# rpiInterface.net
KiCad netlist of a schematic drawn in EAGLE
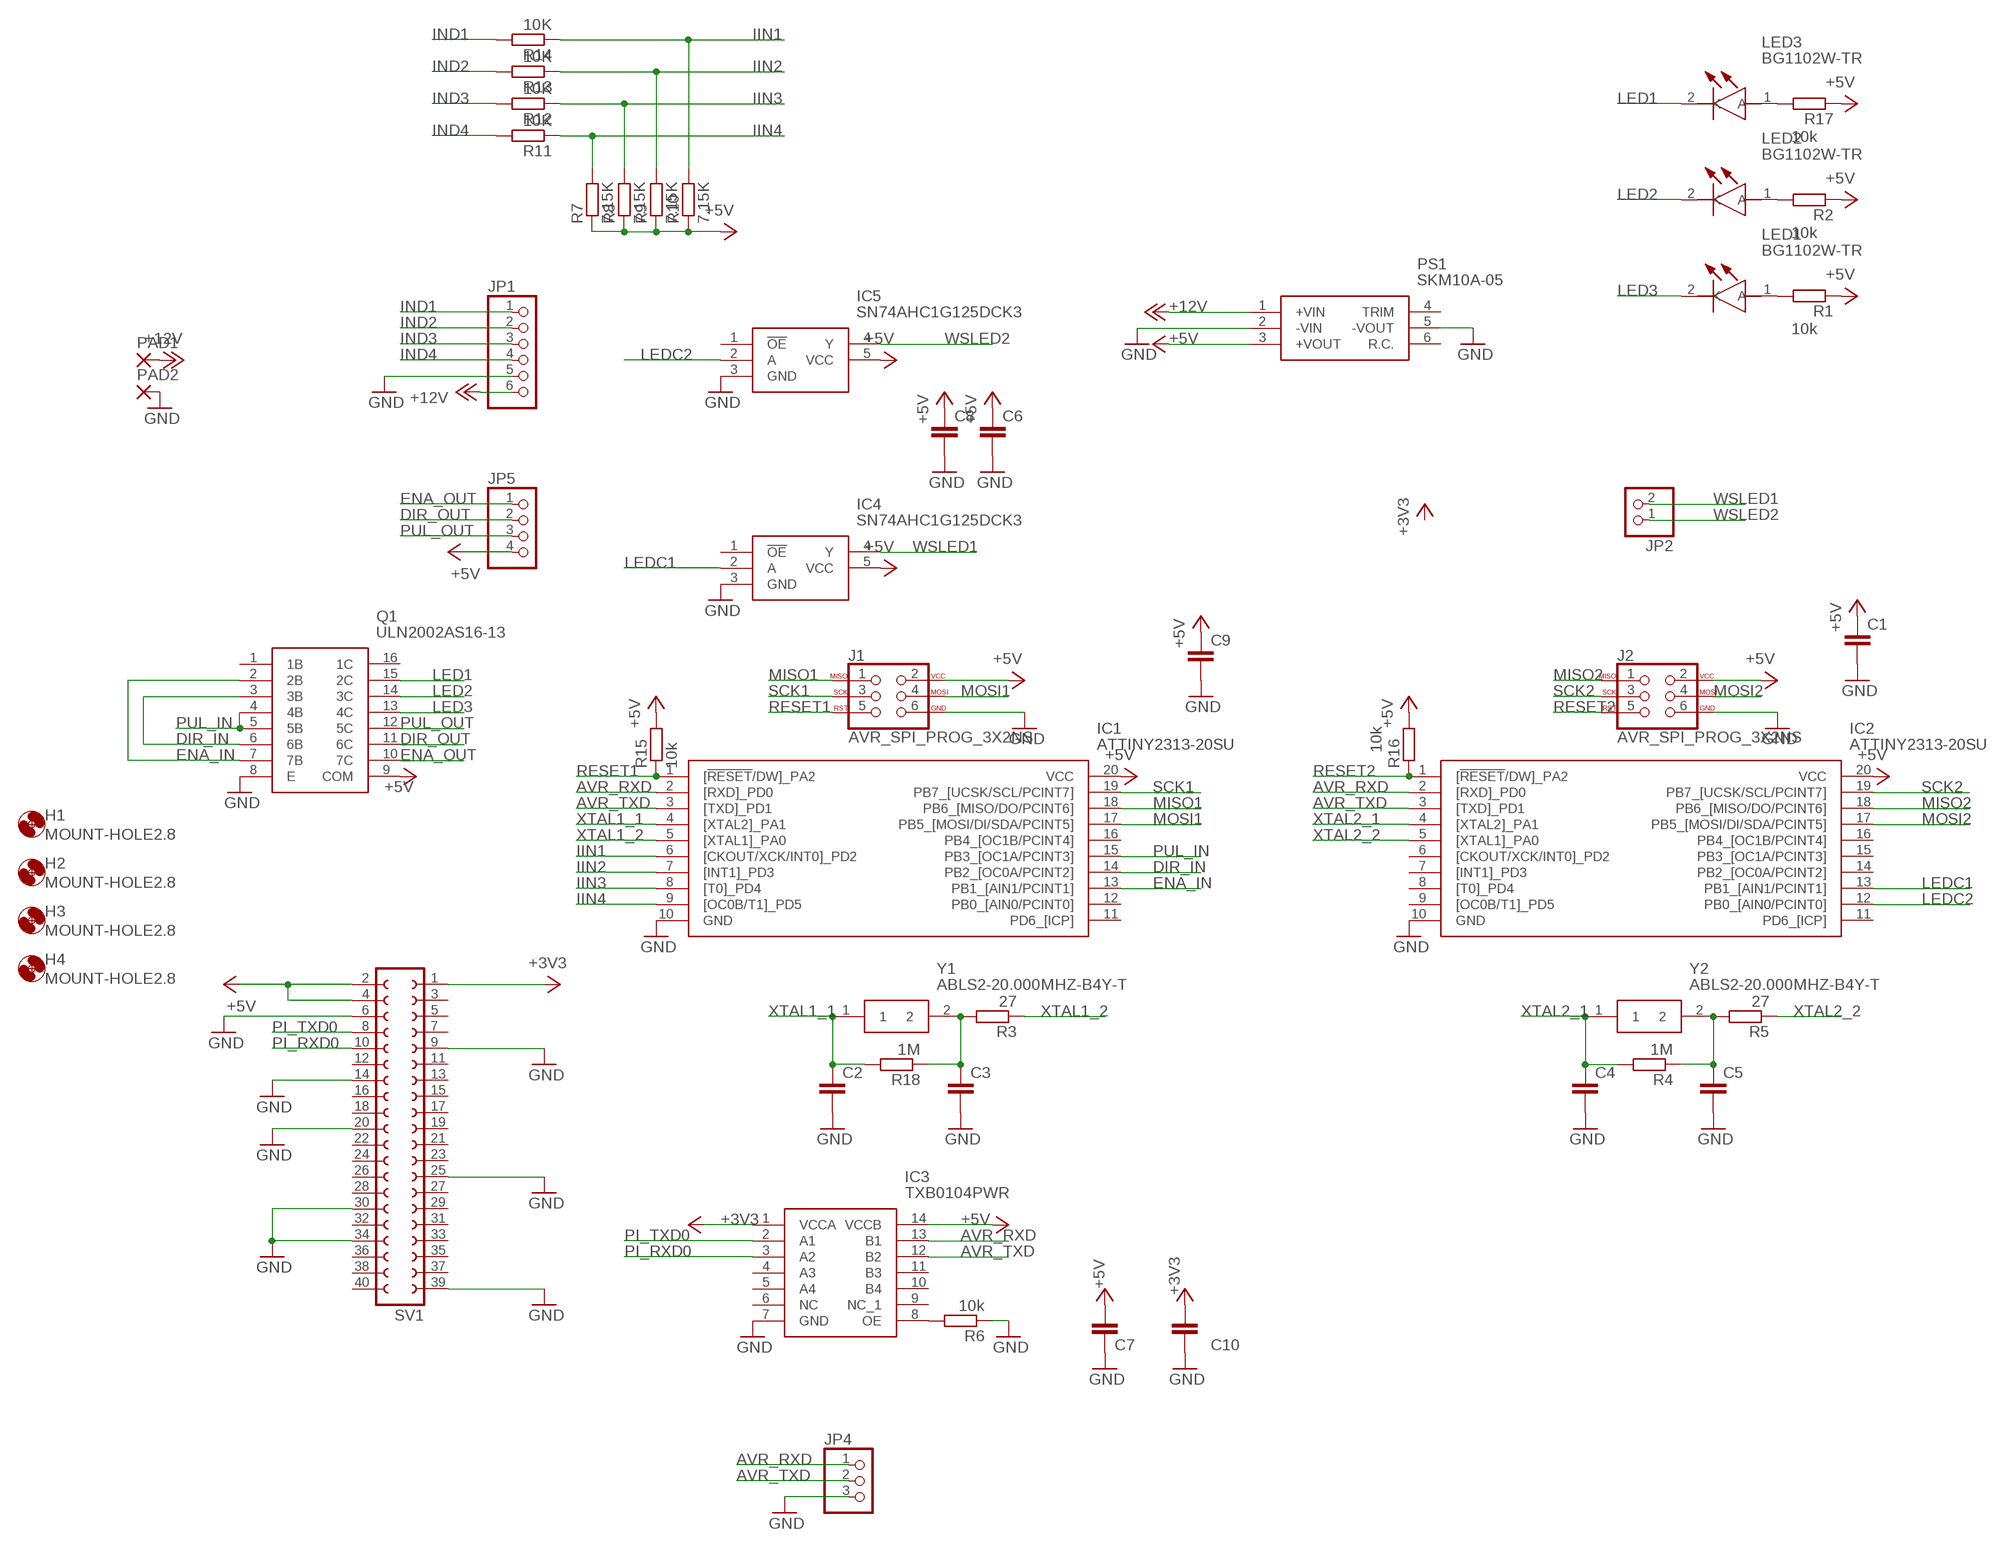
[diagram p0: schematic, sheet 1]

(export (version "E")
  (design (tool "Eeschema 10.0.6"))
  (components
    (comp (ref "C1")
      (value "C-EUC1206")
      (footprint "eagle-import:C1206")
      (libsource (lib "eagle-import") (part "C-EUC1206"))
    )
    (comp (ref "C2")
      (value "C-EUC1206")
      (footprint "eagle-import:C1206")
      (libsource (lib "eagle-import") (part "C-EUC1206"))
    )
    (comp (ref "C3")
      (value "C-EUC1206")
      (footprint "eagle-import:C1206")
      (libsource (lib "eagle-import") (part "C-EUC1206"))
    )
    (comp (ref "C4")
      (value "C-EUC1206")
      (footprint "eagle-import:C1206")
      (libsource (lib "eagle-import") (part "C-EUC1206"))
    )
    (comp (ref "C5")
      (value "C-EUC1206")
      (footprint "eagle-import:C1206")
      (libsource (lib "eagle-import") (part "C-EUC1206"))
    )
    (comp (ref "C6")
      (value "C-EUC1206")
      (footprint "eagle-import:C1206")
      (libsource (lib "eagle-import") (part "C-EUC1206"))
    )
    (comp (ref "C7")
      (value "C-EUC1206")
      (footprint "eagle-import:C1206")
      (libsource (lib "eagle-import") (part "C-EUC1206"))
    )
    (comp (ref "C8")
      (value "C-EUC1206")
      (footprint "eagle-import:C1206")
      (libsource (lib "eagle-import") (part "C-EUC1206"))
    )
    (comp (ref "C9")
      (value "C-EUC1206")
      (footprint "eagle-import:C1206")
      (libsource (lib "eagle-import") (part "C-EUC1206"))
    )
    (comp (ref "C10")
      (value "C-EUC1206")
      (footprint "eagle-import:C1206")
      (libsource (lib "eagle-import") (part "C-EUC1206"))
    )
    (comp (ref "H1")
      (value "MOUNT-HOLE2.8")
      (footprint "eagle-import:2,8")
      (libsource (lib "eagle-import") (part "MOUNT-HOLE2.8"))
    )
    (comp (ref "H2")
      (value "MOUNT-HOLE2.8")
      (footprint "eagle-import:2,8")
      (libsource (lib "eagle-import") (part "MOUNT-HOLE2.8"))
    )
    (comp (ref "H3")
      (value "MOUNT-HOLE2.8")
      (footprint "eagle-import:2,8")
      (libsource (lib "eagle-import") (part "MOUNT-HOLE2.8"))
    )
    (comp (ref "H4")
      (value "MOUNT-HOLE2.8")
      (footprint "eagle-import:2,8")
      (libsource (lib "eagle-import") (part "MOUNT-HOLE2.8"))
    )
    (comp (ref "IC1")
      (value "ATTINY2313-20SU")
      (footprint "eagle-import:SOIC127P1032X265-20N")
      (fields (field (name "MOUSER_PART_NUMBER") "556-ATTINY2313-20SU"))
      (libsource (lib "eagle-import") (part "ATTINY2313-20SU"))
    )
    (comp (ref "IC2")
      (value "ATTINY2313-20SU")
      (footprint "eagle-import:SOIC127P1032X265-20N")
      (fields (field (name "MOUSER_PART_NUMBER") "556-ATTINY2313-20SU"))
      (libsource (lib "eagle-import") (part "ATTINY2313-20SU"))
    )
    (comp (ref "IC3")
      (value "TXB0104PWR")
      (footprint "eagle-import:SOP65P640X120-14N")
      (fields (field (name "MOUSER_PART_NUMBER") "595-TXB0104PWR"))
      (libsource (lib "eagle-import") (part "TXB0104PWR"))
    )
    (comp (ref "IC4")
      (value "SN74AHC1G125DCK3")
      (footprint "eagle-import:SOT65P210X110-5N")
      (fields (field (name "MOUSER_PART_NUMBER") "595-SN74AHC1G125DCK3"))
      (libsource (lib "eagle-import") (part "SN74AHC1G125DCK3"))
    )
    (comp (ref "IC5")
      (value "SN74AHC1G125DCK3")
      (footprint "eagle-import:SOT65P210X110-5N")
      (fields (field (name "MOUSER_PART_NUMBER") "595-SN74AHC1G125DCK3"))
      (libsource (lib "eagle-import") (part "SN74AHC1G125DCK3"))
    )
    (comp (ref "J1")
      (value "AVR_SPI_PROG_3X2NS")
      (footprint "eagle-import:2X3-NS")
      (libsource (lib "eagle-import") (part "AVR_SPI_PROG_3X2NS"))
    )
    (comp (ref "J2")
      (value "AVR_SPI_PROG_3X2NS")
      (footprint "eagle-import:2X3-NS")
      (libsource (lib "eagle-import") (part "AVR_SPI_PROG_3X2NS"))
    )
    (comp (ref "JP1")
      (value "PINHD-1X6")
      (footprint "eagle-import:1X06")
      (libsource (lib "eagle-import") (part "PINHD-1X6"))
    )
    (comp (ref "JP2")
      (value "PINHD-1X2")
      (footprint "eagle-import:1X02")
      (libsource (lib "eagle-import") (part "PINHD-1X2"))
    )
    (comp (ref "JP4")
      (value "PINHD-1X3")
      (footprint "eagle-import:1X03")
      (libsource (lib "eagle-import") (part "PINHD-1X3"))
    )
    (comp (ref "JP5")
      (value "PINHD-1X4")
      (footprint "eagle-import:1X04")
      (libsource (lib "eagle-import") (part "PINHD-1X4"))
    )
    (comp (ref "LED1")
      (value "BG1102W-TR")
      (footprint "eagle-import:BG1102WTR")
      (fields (field (name "MOUSER_PART_NUMBER") "327-BG1102WTR"))
      (libsource (lib "eagle-import") (part "BG1102W-TR"))
    )
    (comp (ref "LED2")
      (value "BG1102W-TR")
      (footprint "eagle-import:BG1102WTR")
      (fields (field (name "MOUSER_PART_NUMBER") "327-BG1102WTR"))
      (libsource (lib "eagle-import") (part "BG1102W-TR"))
    )
    (comp (ref "LED3")
      (value "BG1102W-TR")
      (footprint "eagle-import:BG1102WTR")
      (fields (field (name "MOUSER_PART_NUMBER") "327-BG1102WTR"))
      (libsource (lib "eagle-import") (part "BG1102W-TR"))
    )
    (comp (ref "PAD1")
      (value "3,17/1,3")
      (footprint "eagle-import:3,17_1,3")
      (libsource (lib "eagle-import") (part "3,17/1,3"))
    )
    (comp (ref "PAD2")
      (value "3,17/1,3")
      (footprint "eagle-import:3,17_1,3")
      (libsource (lib "eagle-import") (part "3,17/1,3"))
    )
    (comp (ref "PS1")
      (value "SKM10A-05")
      (footprint "eagle-import:SKM10A05")
      (fields (field (name "MOUSER_PART_NUMBER") "709-SKM10A-05"))
      (libsource (lib "eagle-import") (part "SKM10A-05"))
    )
    (comp (ref "Q1")
      (value "ULN2002AS16-13")
      (footprint "eagle-import:SOIC127P605X126-16N")
      (fields (field (name "MOUSER_PART_NUMBER") "621-ULN2002AS16-13"))
      (libsource (lib "eagle-import") (part "ULN2002AS16-13"))
    )
    (comp (ref "R1")
      (value "10k")
      (footprint "eagle-import:R1206")
      (libsource (lib "eagle-import") (part "R-EU_R1206"))
    )
    (comp (ref "R2")
      (value "10k")
      (footprint "eagle-import:R1206")
      (libsource (lib "eagle-import") (part "R-EU_R1206"))
    )
    (comp (ref "R3")
      (value "27")
      (footprint "eagle-import:R1206")
      (libsource (lib "eagle-import") (part "R-EU_R1206"))
    )
    (comp (ref "R4")
      (value "1M")
      (footprint "eagle-import:R1206")
      (libsource (lib "eagle-import") (part "R-EU_R1206"))
    )
    (comp (ref "R5")
      (value "27")
      (footprint "eagle-import:R1206")
      (libsource (lib "eagle-import") (part "R-EU_R1206"))
    )
    (comp (ref "R6")
      (value "10k")
      (footprint "eagle-import:R1206")
      (libsource (lib "eagle-import") (part "R-EU_R1206"))
    )
    (comp (ref "R7")
      (value "7.15K")
      (footprint "eagle-import:R1206")
      (libsource (lib "eagle-import") (part "R-EU_R1206"))
    )
    (comp (ref "R8")
      (value "7.15K")
      (footprint "eagle-import:R1206")
      (libsource (lib "eagle-import") (part "R-EU_R1206"))
    )
    (comp (ref "R9")
      (value "7.15K")
      (footprint "eagle-import:R1206")
      (libsource (lib "eagle-import") (part "R-EU_R1206"))
    )
    (comp (ref "R10")
      (value "7.15K")
      (footprint "eagle-import:R1206")
      (libsource (lib "eagle-import") (part "R-EU_R1206"))
    )
    (comp (ref "R11")
      (value "10K")
      (footprint "eagle-import:R1206")
      (libsource (lib "eagle-import") (part "R-EU_R1206"))
    )
    (comp (ref "R12")
      (value "10K")
      (footprint "eagle-import:R1206")
      (libsource (lib "eagle-import") (part "R-EU_R1206"))
    )
    (comp (ref "R13")
      (value "10K")
      (footprint "eagle-import:R1206")
      (libsource (lib "eagle-import") (part "R-EU_R1206"))
    )
    (comp (ref "R14")
      (value "10K")
      (footprint "eagle-import:R1206")
      (libsource (lib "eagle-import") (part "R-EU_R1206"))
    )
    (comp (ref "R15")
      (value "10k")
      (footprint "eagle-import:R1206")
      (libsource (lib "eagle-import") (part "R-EU_R1206"))
    )
    (comp (ref "R16")
      (value "10k")
      (footprint "eagle-import:R1206")
      (libsource (lib "eagle-import") (part "R-EU_R1206"))
    )
    (comp (ref "R17")
      (value "10k")
      (footprint "eagle-import:R1206")
      (libsource (lib "eagle-import") (part "R-EU_R1206"))
    )
    (comp (ref "R18")
      (value "1M")
      (footprint "eagle-import:R1206")
      (libsource (lib "eagle-import") (part "R-EU_R1206"))
    )
    (comp (ref "SV1")
      (value "FE20-2")
      (footprint "eagle-import:FE20-2")
      (libsource (lib "eagle-import") (part "FE20-2"))
    )
    (comp (ref "Y1")
      (value "ABLS2-20.000MHZ-B4Y-T")
      (footprint "eagle-import:HC_49US-(AT49)_1")
      (fields
        (field (name "MANUFACTURER_PART_NUMBER") "ABLS2-20.000MHz-B4Y-T")
        (field (name "MOUSER_PART_NUMBER") "815-ABLS2-20-B4YT")
      )
      (libsource (lib "eagle-import") (part "ABLS2-20.000MHZ-B4Y-T"))
    )
    (comp (ref "Y2")
      (value "ABLS2-20.000MHZ-B4Y-T")
      (footprint "eagle-import:HC_49US-(AT49)_1")
      (fields
        (field (name "MANUFACTURER_PART_NUMBER") "ABLS2-20.000MHz-B4Y-T")
        (field (name "MOUSER_PART_NUMBER") "815-ABLS2-20-B4YT")
      )
      (libsource (lib "eagle-import") (part "ABLS2-20.000MHZ-B4Y-T"))
    )
  )
  (nets
    (net (code "1") (name "+3V3") (class "Default")
      (node (ref "C10") (pin "1") (pinfunction "1_1") (pintype "passive"))
      (node (ref "IC3") (pin "1") (pinfunction "VCCA_1") (pintype "power_in"))
      (node (ref "SV1") (pin "1") (pinfunction "1_1") (pintype "passive"))
    )
    (net (code "2") (name "+5V") (class "Default")
      (node (ref "C1") (pin "1") (pinfunction "1_1") (pintype "passive"))
      (node (ref "C6") (pin "1") (pinfunction "1_1") (pintype "passive"))
      (node (ref "C7") (pin "1") (pinfunction "1_1") (pintype "passive"))
      (node (ref "C8") (pin "1") (pinfunction "1_1") (pintype "passive"))
      (node (ref "C9") (pin "1") (pinfunction "1_1") (pintype "passive"))
      (node (ref "IC1") (pin "20") (pinfunction "VCC_20") (pintype "power_in"))
      (node (ref "IC2") (pin "20") (pinfunction "VCC_20") (pintype "power_in"))
      (node (ref "IC3") (pin "14") (pinfunction "VCCB_14") (pintype "power_in"))
      (node (ref "IC4") (pin "5") (pinfunction "VCC_5") (pintype "bidirectional"))
      (node (ref "IC5") (pin "5") (pinfunction "VCC_5") (pintype "bidirectional"))
      (node (ref "J1") (pin "2") (pinfunction "2_2") (pintype "passive"))
      (node (ref "J2") (pin "2") (pinfunction "2_2") (pintype "passive"))
      (node (ref "JP5") (pin "4") (pinfunction "4_4") (pintype "passive"))
      (node (ref "PS1") (pin "3") (pinfunction "+VOUT_3") (pintype "bidirectional"))
      (node (ref "Q1") (pin "9") (pinfunction "COM_9") (pintype "bidirectional"))
      (node (ref "R1") (pin "1") (pinfunction "1_1") (pintype "passive"))
      (node (ref "R10") (pin "1") (pinfunction "1_1") (pintype "passive"))
      (node (ref "R15") (pin "2") (pinfunction "2_2") (pintype "passive"))
      (node (ref "R16") (pin "2") (pinfunction "2_2") (pintype "passive"))
      (node (ref "R17") (pin "1") (pinfunction "1_1") (pintype "passive"))
      (node (ref "R2") (pin "1") (pinfunction "1_1") (pintype "passive"))
      (node (ref "R7") (pin "1") (pinfunction "1_1") (pintype "passive"))
      (node (ref "R8") (pin "1") (pinfunction "1_1") (pintype "passive"))
      (node (ref "R9") (pin "1") (pinfunction "1_1") (pintype "passive"))
      (node (ref "SV1") (pin "2") (pinfunction "2_2") (pintype "passive"))
      (node (ref "SV1") (pin "4") (pinfunction "4_4") (pintype "passive"))
    )
    (net (code "3") (name "+12V") (class "Default")
      (node (ref "JP1") (pin "6") (pinfunction "6_6") (pintype "passive"))
      (node (ref "PAD1") (pin "1") (pinfunction "P_1") (pintype "passive"))
      (node (ref "PS1") (pin "1") (pinfunction "+VIN_1") (pintype "bidirectional"))
    )
    (net (code "4") (name "/AVR_RXD") (class "Default")
      (node (ref "IC1") (pin "2") (pinfunction "[RXD]_PD0_2") (pintype "bidirectional"))
      (node (ref "IC2") (pin "2") (pinfunction "[RXD]_PD0_2") (pintype "bidirectional"))
      (node (ref "IC3") (pin "13") (pinfunction "B1_13") (pintype "bidirectional"))
      (node (ref "JP4") (pin "1") (pinfunction "1_1") (pintype "passive"))
    )
    (net (code "5") (name "/AVR_TXD") (class "Default")
      (node (ref "IC1") (pin "3") (pinfunction "[TXD]_PD1_3") (pintype "bidirectional"))
      (node (ref "IC2") (pin "3") (pinfunction "[TXD]_PD1_3") (pintype "bidirectional"))
      (node (ref "IC3") (pin "12") (pinfunction "B2_12") (pintype "bidirectional"))
      (node (ref "JP4") (pin "2") (pinfunction "2_2") (pintype "passive"))
    )
    (net (code "6") (name "/DIR_IN") (class "Default")
      (node (ref "IC1") (pin "14") (pinfunction "PB2_[OC0A/PCINT2]_14") (pintype "input"))
      (node (ref "Q1") (pin "3") (pinfunction "3B_3") (pintype "bidirectional"))
      (node (ref "Q1") (pin "6") (pinfunction "6B_6") (pintype "bidirectional"))
    )
    (net (code "7") (name "/DIR_OUT") (class "Default")
      (node (ref "JP5") (pin "2") (pinfunction "2_2") (pintype "passive"))
      (node (ref "Q1") (pin "11") (pinfunction "6C_11") (pintype "bidirectional"))
    )
    (net (code "8") (name "/ENA_IN") (class "Default")
      (node (ref "IC1") (pin "13") (pinfunction "PB1_[AIN1/PCINT1]_13") (pintype "input"))
      (node (ref "Q1") (pin "2") (pinfunction "2B_2") (pintype "bidirectional"))
      (node (ref "Q1") (pin "7") (pinfunction "7B_7") (pintype "bidirectional"))
    )
    (net (code "9") (name "/ENA_OUT") (class "Default")
      (node (ref "JP5") (pin "1") (pinfunction "1_1") (pintype "passive"))
      (node (ref "Q1") (pin "10") (pinfunction "7C_10") (pintype "bidirectional"))
    )
    (net (code "10") (name "/IIN1") (class "Default")
      (node (ref "IC1") (pin "6") (pinfunction "[CKOUT/XCK/INT0]_PD2_6") (pintype "output"))
      (node (ref "R10") (pin "2") (pinfunction "2_2") (pintype "passive"))
      (node (ref "R14") (pin "1") (pinfunction "1_1") (pintype "passive"))
    )
    (net (code "11") (name "/IIN2") (class "Default")
      (node (ref "IC1") (pin "7") (pinfunction "[INT1]_PD3_7") (pintype "input"))
      (node (ref "R13") (pin "1") (pinfunction "1_1") (pintype "passive"))
      (node (ref "R9") (pin "2") (pinfunction "2_2") (pintype "passive"))
    )
    (net (code "12") (name "/IIN3") (class "Default")
      (node (ref "IC1") (pin "8") (pinfunction "[T0]_PD4_8") (pintype "bidirectional"))
      (node (ref "R12") (pin "1") (pinfunction "1_1") (pintype "passive"))
      (node (ref "R8") (pin "2") (pinfunction "2_2") (pintype "passive"))
    )
    (net (code "13") (name "/IIN4") (class "Default")
      (node (ref "IC1") (pin "9") (pinfunction "[OC0B/T1]_PD5_9") (pintype "bidirectional"))
      (node (ref "R11") (pin "1") (pinfunction "1_1") (pintype "passive"))
      (node (ref "R7") (pin "2") (pinfunction "2_2") (pintype "passive"))
    )
    (net (code "14") (name "/IND1") (class "Default")
      (node (ref "JP1") (pin "1") (pinfunction "1_1") (pintype "passive"))
      (node (ref "R14") (pin "2") (pinfunction "2_2") (pintype "passive"))
    )
    (net (code "15") (name "/IND2") (class "Default")
      (node (ref "JP1") (pin "2") (pinfunction "2_2") (pintype "passive"))
      (node (ref "R13") (pin "2") (pinfunction "2_2") (pintype "passive"))
    )
    (net (code "16") (name "/IND3") (class "Default")
      (node (ref "JP1") (pin "3") (pinfunction "3_3") (pintype "passive"))
      (node (ref "R12") (pin "2") (pinfunction "2_2") (pintype "passive"))
    )
    (net (code "17") (name "/IND4") (class "Default")
      (node (ref "JP1") (pin "4") (pinfunction "4_4") (pintype "passive"))
      (node (ref "R11") (pin "2") (pinfunction "2_2") (pintype "passive"))
    )
    (net (code "18") (name "/LED1") (class "Default")
      (node (ref "LED3") (pin "2") (pinfunction "K_2") (pintype "bidirectional"))
      (node (ref "Q1") (pin "15") (pinfunction "2C_15") (pintype "bidirectional"))
    )
    (net (code "19") (name "/LED2") (class "Default")
      (node (ref "LED2") (pin "2") (pinfunction "K_2") (pintype "bidirectional"))
      (node (ref "Q1") (pin "14") (pinfunction "3C_14") (pintype "bidirectional"))
    )
    (net (code "20") (name "/LED3") (class "Default")
      (node (ref "LED1") (pin "2") (pinfunction "K_2") (pintype "bidirectional"))
      (node (ref "Q1") (pin "13") (pinfunction "4C_13") (pintype "bidirectional"))
    )
    (net (code "21") (name "/LEDC1") (class "Default")
      (node (ref "IC2") (pin "13") (pinfunction "PB1_[AIN1/PCINT1]_13") (pintype "input"))
      (node (ref "IC4") (pin "2") (pinfunction "A_2") (pintype "bidirectional"))
    )
    (net (code "22") (name "/LEDC2") (class "Default")
      (node (ref "IC2") (pin "12") (pinfunction "PB0_[AIN0/PCINT0]_12") (pintype "input"))
      (node (ref "IC5") (pin "2") (pinfunction "A_2") (pintype "bidirectional"))
    )
    (net (code "23") (name "/MISO1") (class "Default")
      (node (ref "IC1") (pin "18") (pinfunction "PB6_[MISO/DO/PCINT6]_18") (pintype "input"))
      (node (ref "J1") (pin "1") (pinfunction "1_1") (pintype "passive"))
    )
    (net (code "24") (name "/MISO2") (class "Default")
      (node (ref "IC2") (pin "18") (pinfunction "PB6_[MISO/DO/PCINT6]_18") (pintype "input"))
      (node (ref "J2") (pin "1") (pinfunction "1_1") (pintype "passive"))
    )
    (net (code "25") (name "/MOSI1") (class "Default")
      (node (ref "IC1") (pin "17") (pinfunction "PB5_[MOSI/DI/SDA/PCINT5]_17") (pintype "input"))
      (node (ref "J1") (pin "4") (pinfunction "4_4") (pintype "passive"))
    )
    (net (code "26") (name "/MOSI2") (class "Default")
      (node (ref "IC2") (pin "17") (pinfunction "PB5_[MOSI/DI/SDA/PCINT5]_17") (pintype "input"))
      (node (ref "J2") (pin "4") (pinfunction "4_4") (pintype "passive"))
    )
    (net (code "27") (name "/PI_RXD0") (class "Default")
      (node (ref "IC3") (pin "3") (pinfunction "A2_3") (pintype "bidirectional"))
      (node (ref "SV1") (pin "10") (pinfunction "10_10") (pintype "passive"))
    )
    (net (code "28") (name "/PI_TXD0") (class "Default")
      (node (ref "IC3") (pin "2") (pinfunction "A1_2") (pintype "bidirectional"))
      (node (ref "SV1") (pin "8") (pinfunction "8_8") (pintype "passive"))
    )
    (net (code "29") (name "/PUL_IN") (class "Default")
      (node (ref "IC1") (pin "15") (pinfunction "PB3_[OC1A/PCINT3]_15") (pintype "input"))
      (node (ref "Q1") (pin "4") (pinfunction "4B_4") (pintype "bidirectional"))
      (node (ref "Q1") (pin "5") (pinfunction "5B_5") (pintype "bidirectional"))
    )
    (net (code "30") (name "/PUL_OUT") (class "Default")
      (node (ref "JP5") (pin "3") (pinfunction "3_3") (pintype "passive"))
      (node (ref "Q1") (pin "12") (pinfunction "5C_12") (pintype "bidirectional"))
    )
    (net (code "31") (name "/RESET1") (class "Default")
      (node (ref "IC1") (pin "1") (pinfunction "[~{RESET}/DW]_PA2_1") (pintype "bidirectional"))
      (node (ref "J1") (pin "5") (pinfunction "5_5") (pintype "passive"))
      (node (ref "R15") (pin "1") (pinfunction "1_1") (pintype "passive"))
    )
    (net (code "32") (name "/RESET2") (class "Default")
      (node (ref "IC2") (pin "1") (pinfunction "[~{RESET}/DW]_PA2_1") (pintype "bidirectional"))
      (node (ref "J2") (pin "5") (pinfunction "5_5") (pintype "passive"))
      (node (ref "R16") (pin "1") (pinfunction "1_1") (pintype "passive"))
    )
    (net (code "33") (name "/SCK1") (class "Default")
      (node (ref "IC1") (pin "19") (pinfunction "PB7_[UCSK/SCL/PCINT7]_19") (pintype "input"))
      (node (ref "J1") (pin "3") (pinfunction "3_3") (pintype "passive"))
    )
    (net (code "34") (name "/SCK2") (class "Default")
      (node (ref "IC2") (pin "19") (pinfunction "PB7_[UCSK/SCL/PCINT7]_19") (pintype "input"))
      (node (ref "J2") (pin "3") (pinfunction "3_3") (pintype "passive"))
    )
    (net (code "35") (name "/WSLED1") (class "Default")
      (node (ref "IC4") (pin "4") (pinfunction "Y_4") (pintype "bidirectional"))
      (node (ref "JP2") (pin "2") (pinfunction "2_2") (pintype "passive"))
    )
    (net (code "36") (name "/WSLED2") (class "Default")
      (node (ref "IC5") (pin "4") (pinfunction "Y_4") (pintype "bidirectional"))
      (node (ref "JP2") (pin "1") (pinfunction "1_1") (pintype "passive"))
    )
    (net (code "37") (name "/XTAL1_1") (class "Default")
      (node (ref "C2") (pin "1") (pinfunction "1_1") (pintype "passive"))
      (node (ref "IC1") (pin "4") (pinfunction "[XTAL2]_PA1_4") (pintype "bidirectional"))
      (node (ref "R18") (pin "2") (pinfunction "2_2") (pintype "passive"))
      (node (ref "Y1") (pin "1") (pinfunction "1_1") (pintype "bidirectional"))
    )
    (net (code "38") (name "/XTAL1_2") (class "Default")
      (node (ref "IC1") (pin "5") (pinfunction "[XTAL1]_PA0_5") (pintype "bidirectional"))
      (node (ref "R3") (pin "1") (pinfunction "1_1") (pintype "passive"))
    )
    (net (code "39") (name "/XTAL2_1") (class "Default")
      (node (ref "C4") (pin "1") (pinfunction "1_1") (pintype "passive"))
      (node (ref "IC2") (pin "4") (pinfunction "[XTAL2]_PA1_4") (pintype "bidirectional"))
      (node (ref "R4") (pin "2") (pinfunction "2_2") (pintype "passive"))
      (node (ref "Y2") (pin "1") (pinfunction "1_1") (pintype "bidirectional"))
    )
    (net (code "40") (name "/XTAL2_2") (class "Default")
      (node (ref "IC2") (pin "5") (pinfunction "[XTAL1]_PA0_5") (pintype "bidirectional"))
      (node (ref "R5") (pin "1") (pinfunction "1_1") (pintype "passive"))
    )
    (net (code "41") (name "GND") (class "Default")
      (node (ref "C1") (pin "2") (pinfunction "2_2") (pintype "passive"))
      (node (ref "C10") (pin "2") (pinfunction "2_2") (pintype "passive"))
      (node (ref "C2") (pin "2") (pinfunction "2_2") (pintype "passive"))
      (node (ref "C3") (pin "2") (pinfunction "2_2") (pintype "passive"))
      (node (ref "C4") (pin "2") (pinfunction "2_2") (pintype "passive"))
      (node (ref "C5") (pin "2") (pinfunction "2_2") (pintype "passive"))
      (node (ref "C6") (pin "2") (pinfunction "2_2") (pintype "passive"))
      (node (ref "C7") (pin "2") (pinfunction "2_2") (pintype "passive"))
      (node (ref "C8") (pin "2") (pinfunction "2_2") (pintype "passive"))
      (node (ref "C9") (pin "2") (pinfunction "2_2") (pintype "passive"))
      (node (ref "IC1") (pin "10") (pinfunction "GND_10") (pintype "power_in"))
      (node (ref "IC2") (pin "10") (pinfunction "GND_10") (pintype "power_in"))
      (node (ref "IC3") (pin "7") (pinfunction "GND_7") (pintype "power_in"))
      (node (ref "IC4") (pin "3") (pinfunction "GND_3") (pintype "bidirectional"))
      (node (ref "IC5") (pin "3") (pinfunction "GND_3") (pintype "bidirectional"))
      (node (ref "J1") (pin "6") (pinfunction "6_6") (pintype "passive"))
      (node (ref "J2") (pin "6") (pinfunction "6_6") (pintype "passive"))
      (node (ref "JP1") (pin "5") (pinfunction "5_5") (pintype "passive"))
      (node (ref "JP4") (pin "3") (pinfunction "3_3") (pintype "passive"))
      (node (ref "PAD2") (pin "1") (pinfunction "P_1") (pintype "passive"))
      (node (ref "PS1") (pin "2") (pinfunction "-VIN_2") (pintype "bidirectional"))
      (node (ref "PS1") (pin "5") (pinfunction "-VOUT_5") (pintype "bidirectional"))
      (node (ref "Q1") (pin "8") (pinfunction "E_8") (pintype "bidirectional"))
      (node (ref "R6") (pin "1") (pinfunction "1_1") (pintype "passive"))
      (node (ref "SV1") (pin "14") (pinfunction "14_14") (pintype "passive"))
      (node (ref "SV1") (pin "20") (pinfunction "20_20") (pintype "passive"))
      (node (ref "SV1") (pin "25") (pinfunction "25_25") (pintype "passive"))
      (node (ref "SV1") (pin "30") (pinfunction "30_30") (pintype "passive"))
      (node (ref "SV1") (pin "34") (pinfunction "34_34") (pintype "passive"))
      (node (ref "SV1") (pin "39") (pinfunction "39_39") (pintype "passive"))
      (node (ref "SV1") (pin "6") (pinfunction "6_6") (pintype "passive"))
      (node (ref "SV1") (pin "9") (pinfunction "9_9") (pintype "passive"))
    )
    (net (code "42") (name "Net-(C3-Pad1)") (class "Default")
      (node (ref "C3") (pin "1") (pinfunction "1_1") (pintype "passive"))
      (node (ref "R18") (pin "1") (pinfunction "1_1") (pintype "passive"))
      (node (ref "R3") (pin "2") (pinfunction "2_2") (pintype "passive"))
      (node (ref "Y1") (pin "2") (pinfunction "2_2") (pintype "bidirectional"))
    )
    (net (code "43") (name "Net-(C5-Pad1)") (class "Default")
      (node (ref "C5") (pin "1") (pinfunction "1_1") (pintype "passive"))
      (node (ref "R4") (pin "1") (pinfunction "1_1") (pintype "passive"))
      (node (ref "R5") (pin "2") (pinfunction "2_2") (pintype "passive"))
      (node (ref "Y2") (pin "2") (pinfunction "2_2") (pintype "bidirectional"))
    )
    (net (code "44") (name "Net-(IC3-OE)") (class "Default")
      (node (ref "IC3") (pin "8") (pinfunction "OE_8") (pintype "bidirectional"))
      (node (ref "R6") (pin "2") (pinfunction "2_2") (pintype "passive"))
    )
    (net (code "45") (name "Net-(LED1-A)") (class "Default")
      (node (ref "LED1") (pin "1") (pinfunction "A_1") (pintype "bidirectional"))
      (node (ref "R1") (pin "2") (pinfunction "2_2") (pintype "passive"))
    )
    (net (code "46") (name "Net-(LED2-A)") (class "Default")
      (node (ref "LED2") (pin "1") (pinfunction "A_1") (pintype "bidirectional"))
      (node (ref "R2") (pin "2") (pinfunction "2_2") (pintype "passive"))
    )
    (net (code "47") (name "Net-(LED3-A)") (class "Default")
      (node (ref "LED3") (pin "1") (pinfunction "A_1") (pintype "bidirectional"))
      (node (ref "R17") (pin "2") (pinfunction "2_2") (pintype "passive"))
    )
    (net (code "48") (name "unconnected-(IC1-PB0_[AIN0{slash}PCINT0]-Pad12)") (class "Default")
      (node (ref "IC1") (pin "12") (pinfunction "PB0_[AIN0/PCINT0]_12") (pintype "input"))
    )
    (net (code "49") (name "unconnected-(IC1-PB4_[OC1B{slash}PCINT4]-Pad16)") (class "Default")
      (node (ref "IC1") (pin "16") (pinfunction "PB4_[OC1B/PCINT4]_16") (pintype "input"))
    )
    (net (code "50") (name "unconnected-(IC1-PD6_[ICP]-Pad11)") (class "Default")
      (node (ref "IC1") (pin "11") (pinfunction "PD6_[ICP]_11") (pintype "bidirectional"))
    )
    (net (code "51") (name "unconnected-(IC2-PB2_[OC0A{slash}PCINT2]-Pad14)") (class "Default")
      (node (ref "IC2") (pin "14") (pinfunction "PB2_[OC0A/PCINT2]_14") (pintype "input"))
    )
    (net (code "52") (name "unconnected-(IC2-PB3_[OC1A{slash}PCINT3]-Pad15)") (class "Default")
      (node (ref "IC2") (pin "15") (pinfunction "PB3_[OC1A/PCINT3]_15") (pintype "input"))
    )
    (net (code "53") (name "unconnected-(IC2-PB4_[OC1B{slash}PCINT4]-Pad16)") (class "Default")
      (node (ref "IC2") (pin "16") (pinfunction "PB4_[OC1B/PCINT4]_16") (pintype "input"))
    )
    (net (code "54") (name "unconnected-(IC2-PD6_[ICP]-Pad11)") (class "Default")
      (node (ref "IC2") (pin "11") (pinfunction "PD6_[ICP]_11") (pintype "bidirectional"))
    )
    (net (code "55") (name "unconnected-(IC2-[CKOUT{slash}XCK{slash}INT0]_PD2-Pad6)") (class "Default")
      (node (ref "IC2") (pin "6") (pinfunction "[CKOUT/XCK/INT0]_PD2_6") (pintype "output"))
    )
    (net (code "56") (name "unconnected-(IC2-[INT1]_PD3-Pad7)") (class "Default")
      (node (ref "IC2") (pin "7") (pinfunction "[INT1]_PD3_7") (pintype "input"))
    )
    (net (code "57") (name "unconnected-(IC2-[OC0B{slash}T1]_PD5-Pad9)") (class "Default")
      (node (ref "IC2") (pin "9") (pinfunction "[OC0B/T1]_PD5_9") (pintype "bidirectional"))
    )
    (net (code "58") (name "unconnected-(IC2-[T0]_PD4-Pad8)") (class "Default")
      (node (ref "IC2") (pin "8") (pinfunction "[T0]_PD4_8") (pintype "bidirectional"))
    )
    (net (code "59") (name "unconnected-(IC3-A3-Pad4)") (class "Default")
      (node (ref "IC3") (pin "4") (pinfunction "A3_4") (pintype "bidirectional"))
    )
    (net (code "60") (name "unconnected-(IC3-A4-Pad5)") (class "Default")
      (node (ref "IC3") (pin "5") (pinfunction "A4_5") (pintype "bidirectional"))
    )
    (net (code "61") (name "unconnected-(IC3-B3-Pad11)") (class "Default")
      (node (ref "IC3") (pin "11") (pinfunction "B3_11") (pintype "bidirectional"))
    )
    (net (code "62") (name "unconnected-(IC3-B4-Pad10)") (class "Default")
      (node (ref "IC3") (pin "10") (pinfunction "B4_10") (pintype "bidirectional"))
    )
    (net (code "63") (name "unconnected-(IC3-NC-Pad6)") (class "Default")
      (node (ref "IC3") (pin "6") (pinfunction "NC_6") (pintype "no_connect"))
    )
    (net (code "64") (name "unconnected-(IC3-NC_1-Pad9)") (class "Default")
      (node (ref "IC3") (pin "9") (pinfunction "NC_1_9") (pintype "bidirectional"))
    )
    (net (code "65") (name "unconnected-(IC4-~{OE}-Pad1)") (class "Default")
      (node (ref "IC4") (pin "1") (pinfunction "~{OE}_1") (pintype "bidirectional"))
    )
    (net (code "66") (name "unconnected-(IC5-~{OE}-Pad1)") (class "Default")
      (node (ref "IC5") (pin "1") (pinfunction "~{OE}_1") (pintype "bidirectional"))
    )
    (net (code "67") (name "unconnected-(PS1-R.C.-Pad6)") (class "Default")
      (node (ref "PS1") (pin "6") (pinfunction "R.C._6") (pintype "bidirectional"))
    )
    (net (code "68") (name "unconnected-(PS1-TRIM-Pad4)") (class "Default")
      (node (ref "PS1") (pin "4") (pinfunction "TRIM_4") (pintype "bidirectional"))
    )
    (net (code "69") (name "unconnected-(Q1-1B-Pad1)") (class "Default")
      (node (ref "Q1") (pin "1") (pinfunction "1B_1") (pintype "bidirectional"))
    )
    (net (code "70") (name "unconnected-(Q1-1C-Pad16)") (class "Default")
      (node (ref "Q1") (pin "16") (pinfunction "1C_16") (pintype "bidirectional"))
    )
    (net (code "71") (name "unconnected-(SV1-Pad3)") (class "Default")
      (node (ref "SV1") (pin "3") (pinfunction "3_3") (pintype "passive"))
    )
    (net (code "72") (name "unconnected-(SV1-Pad5)") (class "Default")
      (node (ref "SV1") (pin "5") (pinfunction "5_5") (pintype "passive"))
    )
    (net (code "73") (name "unconnected-(SV1-Pad7)") (class "Default")
      (node (ref "SV1") (pin "7") (pinfunction "7_7") (pintype "passive"))
    )
    (net (code "74") (name "unconnected-(SV1-Pad11)") (class "Default")
      (node (ref "SV1") (pin "11") (pinfunction "11_11") (pintype "passive"))
    )
    (net (code "75") (name "unconnected-(SV1-Pad12)") (class "Default")
      (node (ref "SV1") (pin "12") (pinfunction "12_12") (pintype "passive"))
    )
    (net (code "76") (name "unconnected-(SV1-Pad13)") (class "Default")
      (node (ref "SV1") (pin "13") (pinfunction "13_13") (pintype "passive"))
    )
    (net (code "77") (name "unconnected-(SV1-Pad15)") (class "Default")
      (node (ref "SV1") (pin "15") (pinfunction "15_15") (pintype "passive"))
    )
    (net (code "78") (name "unconnected-(SV1-Pad16)") (class "Default")
      (node (ref "SV1") (pin "16") (pinfunction "16_16") (pintype "passive"))
    )
    (net (code "79") (name "unconnected-(SV1-Pad17)") (class "Default")
      (node (ref "SV1") (pin "17") (pinfunction "17_17") (pintype "passive"))
    )
    (net (code "80") (name "unconnected-(SV1-Pad18)") (class "Default")
      (node (ref "SV1") (pin "18") (pinfunction "18_18") (pintype "passive"))
    )
    (net (code "81") (name "unconnected-(SV1-Pad19)") (class "Default")
      (node (ref "SV1") (pin "19") (pinfunction "19_19") (pintype "passive"))
    )
    (net (code "82") (name "unconnected-(SV1-Pad21)") (class "Default")
      (node (ref "SV1") (pin "21") (pinfunction "21_21") (pintype "passive"))
    )
    (net (code "83") (name "unconnected-(SV1-Pad22)") (class "Default")
      (node (ref "SV1") (pin "22") (pinfunction "22_22") (pintype "passive"))
    )
    (net (code "84") (name "unconnected-(SV1-Pad23)") (class "Default")
      (node (ref "SV1") (pin "23") (pinfunction "23_23") (pintype "passive"))
    )
    (net (code "85") (name "unconnected-(SV1-Pad24)") (class "Default")
      (node (ref "SV1") (pin "24") (pinfunction "24_24") (pintype "passive"))
    )
    (net (code "86") (name "unconnected-(SV1-Pad26)") (class "Default")
      (node (ref "SV1") (pin "26") (pinfunction "26_26") (pintype "passive"))
    )
    (net (code "87") (name "unconnected-(SV1-Pad27)") (class "Default")
      (node (ref "SV1") (pin "27") (pinfunction "27_27") (pintype "passive"))
    )
    (net (code "88") (name "unconnected-(SV1-Pad28)") (class "Default")
      (node (ref "SV1") (pin "28") (pinfunction "28_28") (pintype "passive"))
    )
    (net (code "89") (name "unconnected-(SV1-Pad29)") (class "Default")
      (node (ref "SV1") (pin "29") (pinfunction "29_29") (pintype "passive"))
    )
    (net (code "90") (name "unconnected-(SV1-Pad31)") (class "Default")
      (node (ref "SV1") (pin "31") (pinfunction "31_31") (pintype "passive"))
    )
    (net (code "91") (name "unconnected-(SV1-Pad32)") (class "Default")
      (node (ref "SV1") (pin "32") (pinfunction "32_32") (pintype "passive"))
    )
    (net (code "92") (name "unconnected-(SV1-Pad33)") (class "Default")
      (node (ref "SV1") (pin "33") (pinfunction "33_33") (pintype "passive"))
    )
    (net (code "93") (name "unconnected-(SV1-Pad35)") (class "Default")
      (node (ref "SV1") (pin "35") (pinfunction "35_35") (pintype "passive"))
    )
    (net (code "94") (name "unconnected-(SV1-Pad36)") (class "Default")
      (node (ref "SV1") (pin "36") (pinfunction "36_36") (pintype "passive"))
    )
    (net (code "95") (name "unconnected-(SV1-Pad37)") (class "Default")
      (node (ref "SV1") (pin "37") (pinfunction "37_37") (pintype "passive"))
    )
    (net (code "96") (name "unconnected-(SV1-Pad38)") (class "Default")
      (node (ref "SV1") (pin "38") (pinfunction "38_38") (pintype "passive"))
    )
    (net (code "97") (name "unconnected-(SV1-Pad40)") (class "Default")
      (node (ref "SV1") (pin "40") (pinfunction "40_40") (pintype "passive"))
    )
  )
)
